# SenseTemp_-_CREAES.net
KiCad netlist of a schematic drawn in EAGLE
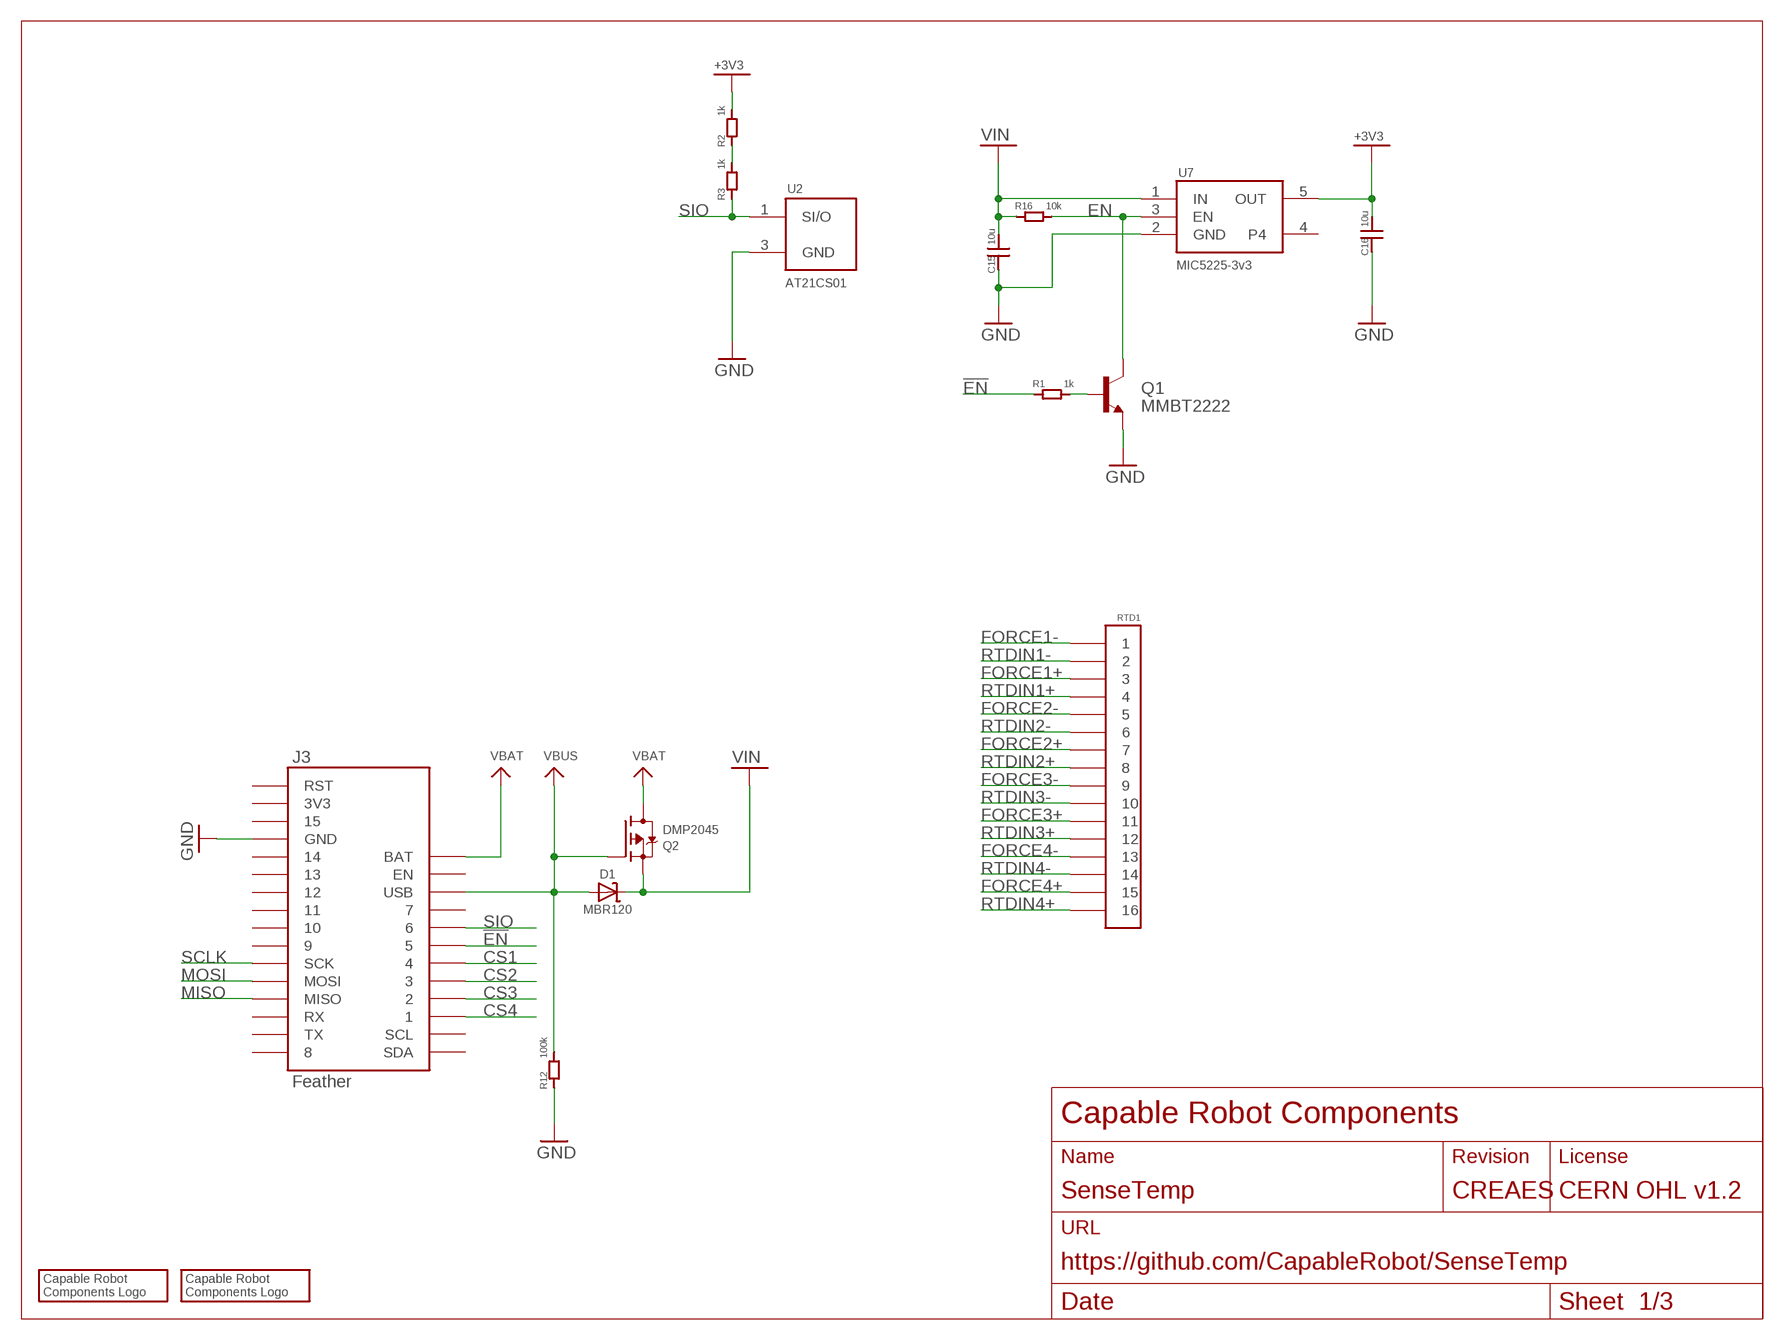
[diagram p0: schematic, sheet 1]
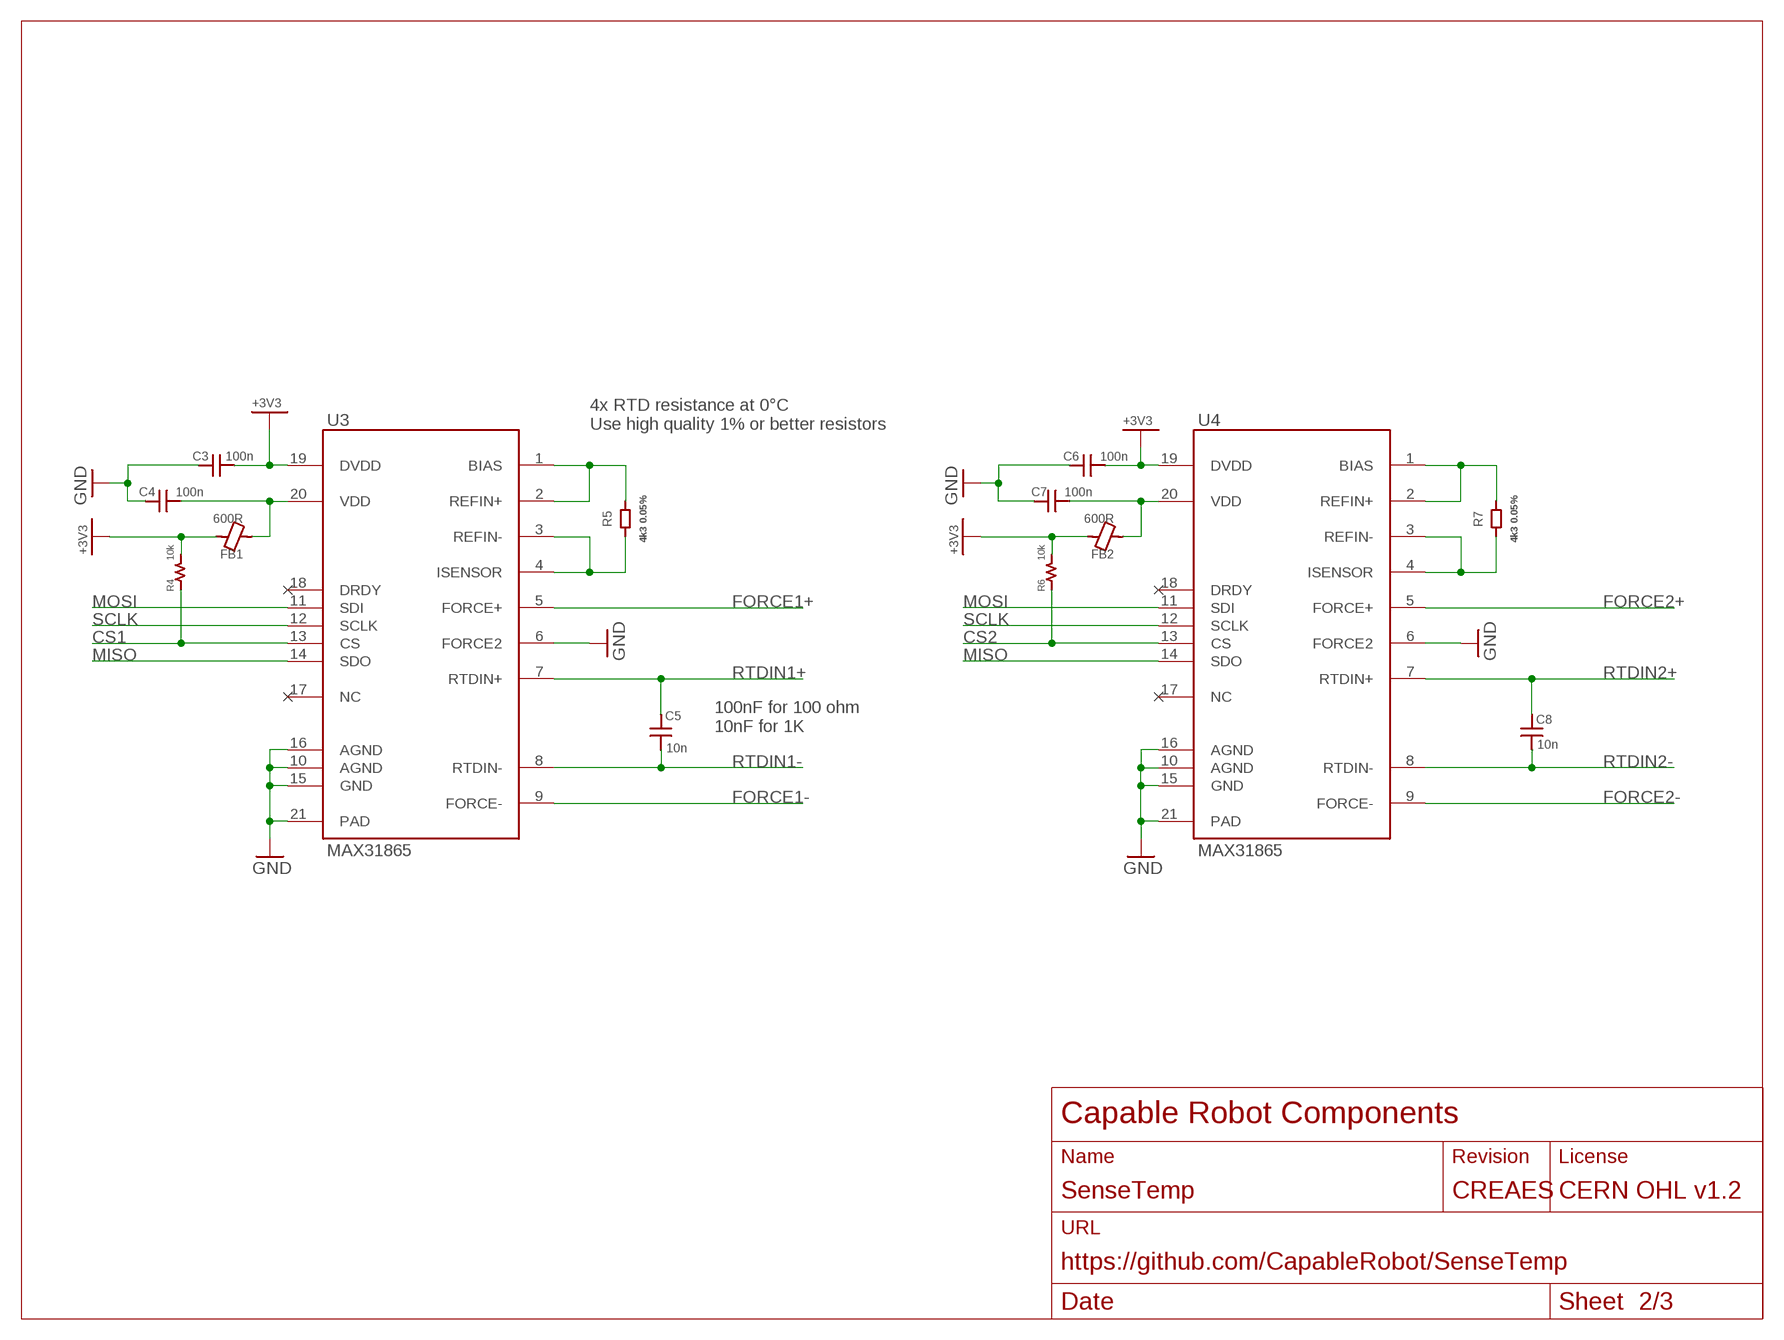
[diagram p1: schematic, sheet 2]
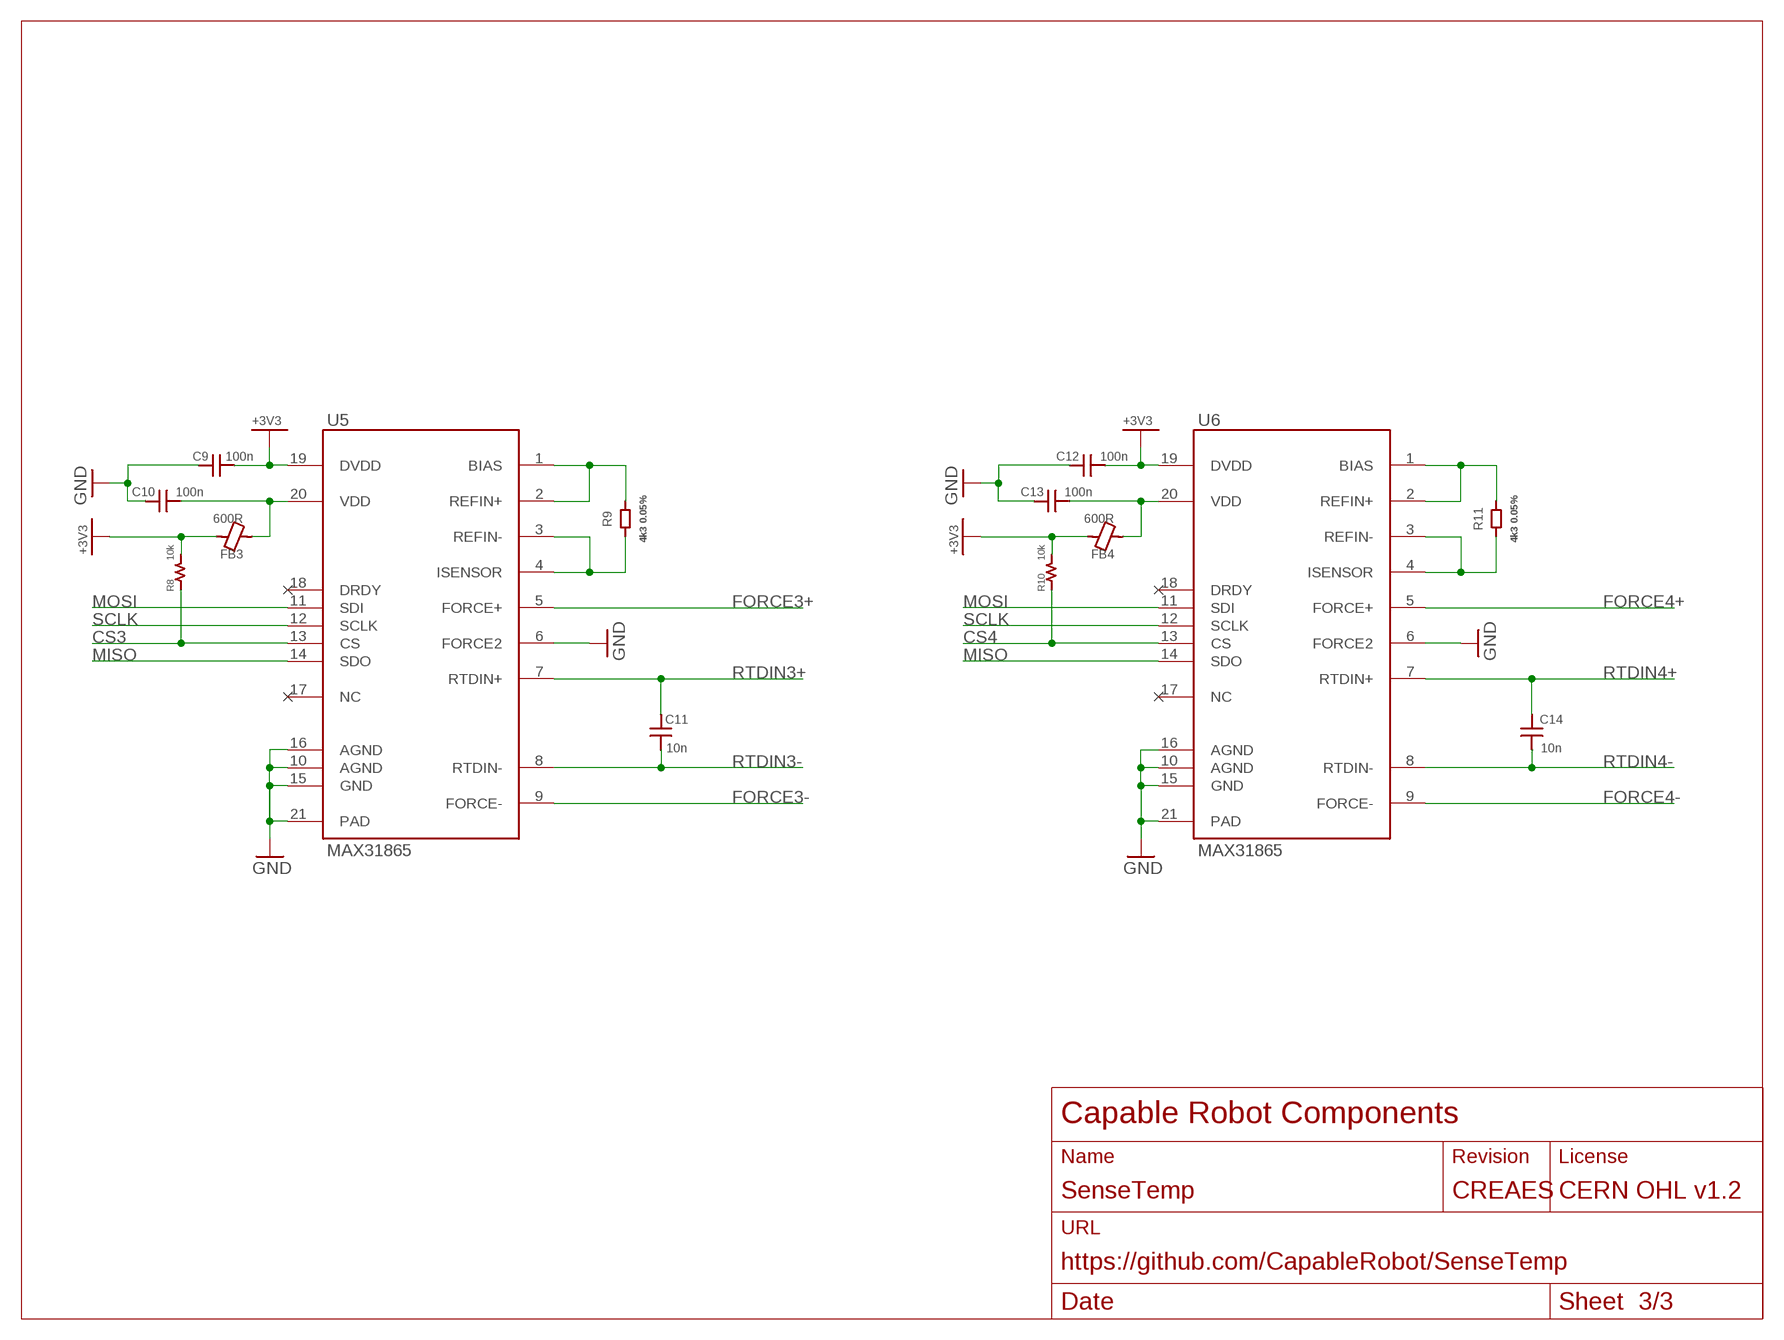
[diagram p2: schematic, sheet 3]

(export (version "E")
  (design (tool "Eeschema 10.0.6"))
  (components
    (comp (ref "C3")
      (value "100n")
      (footprint "eagle-import:0603")
      (libsource (lib "eagle-import") (part "CAP0603"))
    )
    (comp (ref "C4")
      (value "100n")
      (footprint "eagle-import:0603")
      (libsource (lib "eagle-import") (part "CAP0603"))
    )
    (comp (ref "C5")
      (value "10n")
      (footprint "eagle-import:0603")
      (libsource (lib "eagle-import") (part "CAP0603"))
    )
    (comp (ref "C6")
      (value "100n")
      (footprint "eagle-import:0603")
      (libsource (lib "eagle-import") (part "CAP0603"))
    )
    (comp (ref "C7")
      (value "100n")
      (footprint "eagle-import:0603")
      (libsource (lib "eagle-import") (part "CAP0603"))
    )
    (comp (ref "C8")
      (value "10n")
      (footprint "eagle-import:0603")
      (libsource (lib "eagle-import") (part "CAP0603"))
    )
    (comp (ref "FB1")
      (value "600R")
      (footprint "eagle-import:0603")
      (libsource (lib "eagle-import") (part "FER0603"))
    )
    (comp (ref "FB2")
      (value "600R")
      (footprint "eagle-import:0603")
      (libsource (lib "eagle-import") (part "FER0603"))
    )
    (comp (ref "R4")
      (value "10k")
      (footprint "eagle-import:0603")
      (libsource (lib "eagle-import") (part "RES0603"))
    )
    (comp (ref "R5")
      (value "4k3 0.05%")
      (footprint "eagle-import:0603")
      (libsource (lib "eagle-import") (part "CapableRobot_2153859_RES0603"))
    )
    (comp (ref "R6")
      (value "10k")
      (footprint "eagle-import:0603")
      (libsource (lib "eagle-import") (part "RES0603"))
    )
    (comp (ref "R7")
      (value "4k3 0.05%")
      (footprint "eagle-import:0603")
      (libsource (lib "eagle-import") (part "CapableRobot_2153859_RES0603"))
    )
    (comp (ref "U3")
      (value "MAX31865")
      (footprint "eagle-import:QFN65P500X500X100-21T325")
      (libsource (lib "eagle-import") (part "MAX31865"))
    )
    (comp (ref "U4")
      (value "MAX31865")
      (footprint "eagle-import:QFN65P500X500X100-21T325")
      (libsource (lib "eagle-import") (part "MAX31865"))
    )
    (comp (ref "C9")
      (value "100n")
      (footprint "eagle-import:0603")
      (libsource (lib "eagle-import") (part "CAP0603"))
    )
    (comp (ref "C10")
      (value "100n")
      (footprint "eagle-import:0603")
      (libsource (lib "eagle-import") (part "CAP0603"))
    )
    (comp (ref "C11")
      (value "10n")
      (footprint "eagle-import:0603")
      (libsource (lib "eagle-import") (part "CAP0603"))
    )
    (comp (ref "C12")
      (value "100n")
      (footprint "eagle-import:0603")
      (libsource (lib "eagle-import") (part "CAP0603"))
    )
    (comp (ref "C13")
      (value "100n")
      (footprint "eagle-import:0603")
      (libsource (lib "eagle-import") (part "CAP0603"))
    )
    (comp (ref "C14")
      (value "10n")
      (footprint "eagle-import:0603")
      (libsource (lib "eagle-import") (part "CAP0603"))
    )
    (comp (ref "FB3")
      (value "600R")
      (footprint "eagle-import:0603")
      (libsource (lib "eagle-import") (part "FER0603"))
    )
    (comp (ref "FB4")
      (value "600R")
      (footprint "eagle-import:0603")
      (libsource (lib "eagle-import") (part "FER0603"))
    )
    (comp (ref "R8")
      (value "10k")
      (footprint "eagle-import:0603")
      (libsource (lib "eagle-import") (part "RES0603"))
    )
    (comp (ref "R9")
      (value "4k3 0.05%")
      (footprint "eagle-import:0603")
      (libsource (lib "eagle-import") (part "CapableRobot_2153859_RES0603"))
    )
    (comp (ref "R10")
      (value "10k")
      (footprint "eagle-import:0603")
      (libsource (lib "eagle-import") (part "RES0603"))
    )
    (comp (ref "R11")
      (value "4k3 0.05%")
      (footprint "eagle-import:0603")
      (libsource (lib "eagle-import") (part "CapableRobot_2153859_RES0603"))
    )
    (comp (ref "U5")
      (value "MAX31865")
      (footprint "eagle-import:QFN65P500X500X100-21T325")
      (libsource (lib "eagle-import") (part "MAX31865"))
    )
    (comp (ref "U6")
      (value "MAX31865")
      (footprint "eagle-import:QFN65P500X500X100-21T325")
      (libsource (lib "eagle-import") (part "MAX31865"))
    )
    (comp (ref "C15")
      (value "10u")
      (footprint "eagle-import:0805")
      (libsource (lib "eagle-import") (part "CAP0805"))
    )
    (comp (ref "C16")
      (value "10u")
      (footprint "eagle-import:0805")
      (libsource (lib "eagle-import") (part "CAP0805"))
    )
    (comp (ref "D1")
      (value "MBR120")
      (footprint "eagle-import:SOD-123")
      (fields (field (name "MPN") "MBR120VLSFT3G"))
      (libsource (lib "eagle-import") (part "DIODE-SCHOTTKYSOD-123"))
    )
    (comp (ref "J3")
      (value "FEATHERPTH")
      (footprint "eagle-import:FEATHER-PTH")
      (libsource (lib "eagle-import") (part "FEATHERPTH"))
    )
    (comp (ref "LOGO1")
      (value "CRC-LOGO7SILK")
      (footprint "eagle-import:CRC-LOGO-7-SILK")
      (libsource (lib "eagle-import") (part "CRC-LOGO7SILK"))
    )
    (comp (ref "LOGO2")
      (value "CRC-LOGO5")
      (footprint "eagle-import:CRC-LOGO-5")
      (libsource (lib "eagle-import") (part "CRC-LOGO5"))
    )
    (comp (ref "Q1")
      (value "MMBT2222")
      (footprint "eagle-import:SOT23-3")
      (fields (field (name "MPN") "MMBT2222LT1G"))
      (libsource (lib "eagle-import") (part "TRANSISTOR_NPNSOT23-3"))
    )
    (comp (ref "Q2")
      (value "DMP2045")
      (footprint "eagle-import:SOT23-R")
      (fields (field (name "MPN") "DMP2045U-7"))
      (libsource (lib "eagle-import") (part "MOSFET-P"))
    )
    (comp (ref "R1")
      (value "1k")
      (footprint "eagle-import:0603")
      (libsource (lib "eagle-import") (part "CapableRobot_2153859_RES0603"))
    )
    (comp (ref "R2")
      (value "1k")
      (footprint "eagle-import:0603")
      (libsource (lib "eagle-import") (part "CapableRobot_2153859_RES0603"))
    )
    (comp (ref "R3")
      (value "1k")
      (footprint "eagle-import:0603")
      (libsource (lib "eagle-import") (part "CapableRobot_2153859_RES0603"))
    )
    (comp (ref "R12")
      (value "100k")
      (footprint "eagle-import:0603")
      (libsource (lib "eagle-import") (part "CapableRobot_2153859_RES0603"))
    )
    (comp (ref "R16")
      (value "10k")
      (footprint "eagle-import:0603")
      (libsource (lib "eagle-import") (part "CapableRobot_2153859_RES0603"))
    )
    (comp (ref "RTD1")
      (value "CONN-16ZT")
      (footprint "eagle-import:CONN-2X8-050-SMT-ZT")
      (fields (field (name "MPN") "3221-16-0300-00"))
      (libsource (lib "eagle-import") (part "CONN-16ZT"))
    )
    (comp (ref "U2")
      (value "AT21CS01")
      (footprint "eagle-import:SOT23")
      (libsource (lib "eagle-import") (part "AT21CS01"))
    )
    (comp (ref "U7")
      (value "3v3")
      (footprint "eagle-import:SOT25")
      (libsource (lib "eagle-import") (part "MIC5225"))
    )
  )
  (nets
    (net (code "1") (name "+3V3") (class "Default")
      (node (ref "C12") (pin "1") (pinfunction "P$1_1") (pintype "bidirectional"))
      (node (ref "C16") (pin "2") (pinfunction "P$2_2") (pintype "bidirectional"))
      (node (ref "C3") (pin "1") (pinfunction "P$1_1") (pintype "bidirectional"))
      (node (ref "C6") (pin "1") (pinfunction "P$1_1") (pintype "bidirectional"))
      (node (ref "C9") (pin "1") (pinfunction "P$1_1") (pintype "bidirectional"))
      (node (ref "FB1") (pin "2") (pinfunction "P$2_2") (pintype "bidirectional"))
      (node (ref "FB2") (pin "2") (pinfunction "P$2_2") (pintype "bidirectional"))
      (node (ref "FB3") (pin "2") (pinfunction "P$2_2") (pintype "bidirectional"))
      (node (ref "FB4") (pin "2") (pinfunction "P$2_2") (pintype "bidirectional"))
      (node (ref "R10") (pin "2") (pinfunction "2_2") (pintype "passive"))
      (node (ref "R2") (pin "2") (pinfunction "2_2") (pintype "passive"))
      (node (ref "R4") (pin "2") (pinfunction "2_2") (pintype "passive"))
      (node (ref "R6") (pin "2") (pinfunction "2_2") (pintype "passive"))
      (node (ref "R8") (pin "2") (pinfunction "2_2") (pintype "passive"))
      (node (ref "U3") (pin "19") (pinfunction "DVDD_19") (pintype "bidirectional"))
      (node (ref "U4") (pin "19") (pinfunction "DVDD_19") (pintype "bidirectional"))
      (node (ref "U5") (pin "19") (pinfunction "DVDD_19") (pintype "bidirectional"))
      (node (ref "U6") (pin "19") (pinfunction "DVDD_19") (pintype "bidirectional"))
      (node (ref "U7") (pin "5") (pinfunction "OUT_5") (pintype "bidirectional"))
    )
    (net (code "2") (name "CS1") (class "Default")
      (node (ref "J3") (pin "4") (pinfunction "4_4") (pintype "bidirectional"))
      (node (ref "R4") (pin "1") (pinfunction "1_1") (pintype "passive"))
      (node (ref "U3") (pin "13") (pinfunction "CS_13") (pintype "bidirectional"))
    )
    (net (code "3") (name "CS2") (class "Default")
      (node (ref "J3") (pin "3") (pinfunction "3_3") (pintype "bidirectional"))
      (node (ref "R6") (pin "1") (pinfunction "1_1") (pintype "passive"))
      (node (ref "U4") (pin "13") (pinfunction "CS_13") (pintype "bidirectional"))
    )
    (net (code "4") (name "CS3") (class "Default")
      (node (ref "J3") (pin "2") (pinfunction "2_2") (pintype "bidirectional"))
      (node (ref "R8") (pin "1") (pinfunction "1_1") (pintype "passive"))
      (node (ref "U5") (pin "13") (pinfunction "CS_13") (pintype "bidirectional"))
    )
    (net (code "5") (name "CS4") (class "Default")
      (node (ref "J3") (pin "1") (pinfunction "1_1") (pintype "bidirectional"))
      (node (ref "R10") (pin "1") (pinfunction "1_1") (pintype "passive"))
      (node (ref "U6") (pin "13") (pinfunction "CS_13") (pintype "bidirectional"))
    )
    (net (code "6") (name "EN") (class "Default")
      (node (ref "Q1") (pin "3") (pinfunction "C_3") (pintype "passive"))
      (node (ref "R16") (pin "2") (pinfunction "2_2") (pintype "passive"))
      (node (ref "U7") (pin "3") (pinfunction "EN_3") (pintype "bidirectional"))
    )
    (net (code "7") (name "FORCE1+") (class "Default")
      (node (ref "RTD1") (pin "3") (pinfunction "3_3") (pintype "bidirectional"))
      (node (ref "U3") (pin "5") (pinfunction "FORCE+_5") (pintype "bidirectional"))
    )
    (net (code "8") (name "FORCE1-") (class "Default")
      (node (ref "RTD1") (pin "1") (pinfunction "1_1") (pintype "bidirectional"))
      (node (ref "U3") (pin "9") (pinfunction "FORCE-_9") (pintype "bidirectional"))
    )
    (net (code "9") (name "FORCE2+") (class "Default")
      (node (ref "RTD1") (pin "7") (pinfunction "7_7") (pintype "bidirectional"))
      (node (ref "U4") (pin "5") (pinfunction "FORCE+_5") (pintype "bidirectional"))
    )
    (net (code "10") (name "FORCE2-") (class "Default")
      (node (ref "RTD1") (pin "5") (pinfunction "5_5") (pintype "bidirectional"))
      (node (ref "U4") (pin "9") (pinfunction "FORCE-_9") (pintype "bidirectional"))
    )
    (net (code "11") (name "FORCE3+") (class "Default")
      (node (ref "RTD1") (pin "11") (pinfunction "11_11") (pintype "bidirectional"))
      (node (ref "U5") (pin "5") (pinfunction "FORCE+_5") (pintype "bidirectional"))
    )
    (net (code "12") (name "FORCE3-") (class "Default")
      (node (ref "RTD1") (pin "9") (pinfunction "9_9") (pintype "bidirectional"))
      (node (ref "U5") (pin "9") (pinfunction "FORCE-_9") (pintype "bidirectional"))
    )
    (net (code "13") (name "FORCE4+") (class "Default")
      (node (ref "RTD1") (pin "15") (pinfunction "15_15") (pintype "bidirectional"))
      (node (ref "U6") (pin "5") (pinfunction "FORCE+_5") (pintype "bidirectional"))
    )
    (net (code "14") (name "FORCE4-") (class "Default")
      (node (ref "RTD1") (pin "13") (pinfunction "13_13") (pintype "bidirectional"))
      (node (ref "U6") (pin "9") (pinfunction "FORCE-_9") (pintype "bidirectional"))
    )
    (net (code "15") (name "GND") (class "Default")
      (node (ref "C10") (pin "2") (pinfunction "P$2_2") (pintype "bidirectional"))
      (node (ref "C12") (pin "2") (pinfunction "P$2_2") (pintype "bidirectional"))
      (node (ref "C13") (pin "2") (pinfunction "P$2_2") (pintype "bidirectional"))
      (node (ref "C15") (pin "1") (pinfunction "P$1_1") (pintype "bidirectional"))
      (node (ref "C16") (pin "1") (pinfunction "P$1_1") (pintype "bidirectional"))
      (node (ref "C3") (pin "2") (pinfunction "P$2_2") (pintype "bidirectional"))
      (node (ref "C4") (pin "2") (pinfunction "P$2_2") (pintype "bidirectional"))
      (node (ref "C6") (pin "2") (pinfunction "P$2_2") (pintype "bidirectional"))
      (node (ref "C7") (pin "2") (pinfunction "P$2_2") (pintype "bidirectional"))
      (node (ref "C9") (pin "2") (pinfunction "P$2_2") (pintype "bidirectional"))
      (node (ref "J3") (pin "GND") (pinfunction "GND_GND") (pintype "bidirectional"))
      (node (ref "Q1") (pin "2") (pinfunction "E_2") (pintype "passive"))
      (node (ref "R12") (pin "1") (pinfunction "1_1") (pintype "passive"))
      (node (ref "U2") (pin "3") (pinfunction "GND_3") (pintype "bidirectional"))
      (node (ref "U3") (pin "10") (pinfunction "AGND_10") (pintype "bidirectional"))
      (node (ref "U3") (pin "15") (pinfunction "GND_15") (pintype "bidirectional"))
      (node (ref "U3") (pin "16") (pinfunction "AGND_16") (pintype "bidirectional"))
      (node (ref "U3") (pin "21") (pinfunction "PAD_21") (pintype "bidirectional"))
      (node (ref "U3") (pin "6") (pinfunction "FORCE2_6") (pintype "bidirectional"))
      (node (ref "U4") (pin "10") (pinfunction "AGND_10") (pintype "bidirectional"))
      (node (ref "U4") (pin "15") (pinfunction "GND_15") (pintype "bidirectional"))
      (node (ref "U4") (pin "16") (pinfunction "AGND_16") (pintype "bidirectional"))
      (node (ref "U4") (pin "21") (pinfunction "PAD_21") (pintype "bidirectional"))
      (node (ref "U4") (pin "6") (pinfunction "FORCE2_6") (pintype "bidirectional"))
      (node (ref "U5") (pin "10") (pinfunction "AGND_10") (pintype "bidirectional"))
      (node (ref "U5") (pin "15") (pinfunction "GND_15") (pintype "bidirectional"))
      (node (ref "U5") (pin "16") (pinfunction "AGND_16") (pintype "bidirectional"))
      (node (ref "U5") (pin "21") (pinfunction "PAD_21") (pintype "bidirectional"))
      (node (ref "U5") (pin "6") (pinfunction "FORCE2_6") (pintype "bidirectional"))
      (node (ref "U6") (pin "10") (pinfunction "AGND_10") (pintype "bidirectional"))
      (node (ref "U6") (pin "15") (pinfunction "GND_15") (pintype "bidirectional"))
      (node (ref "U6") (pin "16") (pinfunction "AGND_16") (pintype "bidirectional"))
      (node (ref "U6") (pin "21") (pinfunction "PAD_21") (pintype "bidirectional"))
      (node (ref "U6") (pin "6") (pinfunction "FORCE2_6") (pintype "bidirectional"))
      (node (ref "U7") (pin "2") (pinfunction "GND_2") (pintype "bidirectional"))
    )
    (net (code "16") (name "MISO") (class "Default")
      (node (ref "J3") (pin "MISO") (pinfunction "MISO_MISO") (pintype "bidirectional"))
      (node (ref "U3") (pin "14") (pinfunction "SDO_14") (pintype "bidirectional"))
      (node (ref "U4") (pin "14") (pinfunction "SDO_14") (pintype "bidirectional"))
      (node (ref "U5") (pin "14") (pinfunction "SDO_14") (pintype "bidirectional"))
      (node (ref "U6") (pin "14") (pinfunction "SDO_14") (pintype "bidirectional"))
    )
    (net (code "17") (name "MOSI") (class "Default")
      (node (ref "J3") (pin "MOSI") (pinfunction "MOSI_MOSI") (pintype "bidirectional"))
      (node (ref "U3") (pin "11") (pinfunction "SDI_11") (pintype "bidirectional"))
      (node (ref "U4") (pin "11") (pinfunction "SDI_11") (pintype "bidirectional"))
      (node (ref "U5") (pin "11") (pinfunction "SDI_11") (pintype "bidirectional"))
      (node (ref "U6") (pin "11") (pinfunction "SDI_11") (pintype "bidirectional"))
    )
    (net (code "18") (name "Net-(C4-P$1)") (class "Default")
      (node (ref "C4") (pin "1") (pinfunction "P$1_1") (pintype "bidirectional"))
      (node (ref "FB1") (pin "1") (pinfunction "P$1_1") (pintype "bidirectional"))
      (node (ref "U3") (pin "20") (pinfunction "VDD_20") (pintype "bidirectional"))
    )
    (net (code "19") (name "Net-(C7-P$1)") (class "Default")
      (node (ref "C7") (pin "1") (pinfunction "P$1_1") (pintype "bidirectional"))
      (node (ref "FB2") (pin "1") (pinfunction "P$1_1") (pintype "bidirectional"))
      (node (ref "U4") (pin "20") (pinfunction "VDD_20") (pintype "bidirectional"))
    )
    (net (code "20") (name "Net-(C10-P$1)") (class "Default")
      (node (ref "C10") (pin "1") (pinfunction "P$1_1") (pintype "bidirectional"))
      (node (ref "FB3") (pin "1") (pinfunction "P$1_1") (pintype "bidirectional"))
      (node (ref "U5") (pin "20") (pinfunction "VDD_20") (pintype "bidirectional"))
    )
    (net (code "21") (name "Net-(C13-P$1)") (class "Default")
      (node (ref "C13") (pin "1") (pinfunction "P$1_1") (pintype "bidirectional"))
      (node (ref "FB4") (pin "1") (pinfunction "P$1_1") (pintype "bidirectional"))
      (node (ref "U6") (pin "20") (pinfunction "VDD_20") (pintype "bidirectional"))
    )
    (net (code "22") (name "Net-(Q1-B)") (class "Default")
      (node (ref "Q1") (pin "1") (pinfunction "B_1") (pintype "passive"))
      (node (ref "R1") (pin "2") (pinfunction "2_2") (pintype "passive"))
    )
    (net (code "23") (name "Net-(R2-Pad1)") (class "Default")
      (node (ref "R2") (pin "1") (pinfunction "1_1") (pintype "passive"))
      (node (ref "R3") (pin "2") (pinfunction "2_2") (pintype "passive"))
    )
    (net (code "24") (name "Net-(U3-BIAS)") (class "Default")
      (node (ref "R5") (pin "2") (pinfunction "2_2") (pintype "passive"))
      (node (ref "U3") (pin "1") (pinfunction "BIAS_1") (pintype "bidirectional"))
      (node (ref "U3") (pin "2") (pinfunction "REFIN+_2") (pintype "bidirectional"))
    )
    (net (code "25") (name "Net-(U3-ISENSOR)") (class "Default")
      (node (ref "R5") (pin "1") (pinfunction "1_1") (pintype "passive"))
      (node (ref "U3") (pin "3") (pinfunction "REFIN-_3") (pintype "bidirectional"))
      (node (ref "U3") (pin "4") (pinfunction "ISENSOR_4") (pintype "bidirectional"))
    )
    (net (code "26") (name "Net-(U4-BIAS)") (class "Default")
      (node (ref "R7") (pin "2") (pinfunction "2_2") (pintype "passive"))
      (node (ref "U4") (pin "1") (pinfunction "BIAS_1") (pintype "bidirectional"))
      (node (ref "U4") (pin "2") (pinfunction "REFIN+_2") (pintype "bidirectional"))
    )
    (net (code "27") (name "Net-(U4-ISENSOR)") (class "Default")
      (node (ref "R7") (pin "1") (pinfunction "1_1") (pintype "passive"))
      (node (ref "U4") (pin "3") (pinfunction "REFIN-_3") (pintype "bidirectional"))
      (node (ref "U4") (pin "4") (pinfunction "ISENSOR_4") (pintype "bidirectional"))
    )
    (net (code "28") (name "Net-(U5-BIAS)") (class "Default")
      (node (ref "R9") (pin "2") (pinfunction "2_2") (pintype "passive"))
      (node (ref "U5") (pin "1") (pinfunction "BIAS_1") (pintype "bidirectional"))
      (node (ref "U5") (pin "2") (pinfunction "REFIN+_2") (pintype "bidirectional"))
    )
    (net (code "29") (name "Net-(U5-ISENSOR)") (class "Default")
      (node (ref "R9") (pin "1") (pinfunction "1_1") (pintype "passive"))
      (node (ref "U5") (pin "3") (pinfunction "REFIN-_3") (pintype "bidirectional"))
      (node (ref "U5") (pin "4") (pinfunction "ISENSOR_4") (pintype "bidirectional"))
    )
    (net (code "30") (name "Net-(U6-BIAS)") (class "Default")
      (node (ref "R11") (pin "2") (pinfunction "2_2") (pintype "passive"))
      (node (ref "U6") (pin "1") (pinfunction "BIAS_1") (pintype "bidirectional"))
      (node (ref "U6") (pin "2") (pinfunction "REFIN+_2") (pintype "bidirectional"))
    )
    (net (code "31") (name "Net-(U6-ISENSOR)") (class "Default")
      (node (ref "R11") (pin "1") (pinfunction "1_1") (pintype "passive"))
      (node (ref "U6") (pin "3") (pinfunction "REFIN-_3") (pintype "bidirectional"))
      (node (ref "U6") (pin "4") (pinfunction "ISENSOR_4") (pintype "bidirectional"))
    )
    (net (code "32") (name "RTDIN1+") (class "Default")
      (node (ref "C5") (pin "1") (pinfunction "P$1_1") (pintype "bidirectional"))
      (node (ref "RTD1") (pin "4") (pinfunction "4_4") (pintype "bidirectional"))
      (node (ref "U3") (pin "7") (pinfunction "RTDIN+_7") (pintype "bidirectional"))
    )
    (net (code "33") (name "RTDIN1-") (class "Default")
      (node (ref "C5") (pin "2") (pinfunction "P$2_2") (pintype "bidirectional"))
      (node (ref "RTD1") (pin "2") (pinfunction "2_2") (pintype "bidirectional"))
      (node (ref "U3") (pin "8") (pinfunction "RTDIN-_8") (pintype "bidirectional"))
    )
    (net (code "34") (name "RTDIN2+") (class "Default")
      (node (ref "C8") (pin "1") (pinfunction "P$1_1") (pintype "bidirectional"))
      (node (ref "RTD1") (pin "8") (pinfunction "8_8") (pintype "bidirectional"))
      (node (ref "U4") (pin "7") (pinfunction "RTDIN+_7") (pintype "bidirectional"))
    )
    (net (code "35") (name "RTDIN2-") (class "Default")
      (node (ref "C8") (pin "2") (pinfunction "P$2_2") (pintype "bidirectional"))
      (node (ref "RTD1") (pin "6") (pinfunction "6_6") (pintype "bidirectional"))
      (node (ref "U4") (pin "8") (pinfunction "RTDIN-_8") (pintype "bidirectional"))
    )
    (net (code "36") (name "RTDIN3+") (class "Default")
      (node (ref "C11") (pin "1") (pinfunction "P$1_1") (pintype "bidirectional"))
      (node (ref "RTD1") (pin "12") (pinfunction "12_12") (pintype "bidirectional"))
      (node (ref "U5") (pin "7") (pinfunction "RTDIN+_7") (pintype "bidirectional"))
    )
    (net (code "37") (name "RTDIN3-") (class "Default")
      (node (ref "C11") (pin "2") (pinfunction "P$2_2") (pintype "bidirectional"))
      (node (ref "RTD1") (pin "10") (pinfunction "10_10") (pintype "bidirectional"))
      (node (ref "U5") (pin "8") (pinfunction "RTDIN-_8") (pintype "bidirectional"))
    )
    (net (code "38") (name "RTDIN4+") (class "Default")
      (node (ref "C14") (pin "1") (pinfunction "P$1_1") (pintype "bidirectional"))
      (node (ref "RTD1") (pin "16") (pinfunction "16_16") (pintype "bidirectional"))
      (node (ref "U6") (pin "7") (pinfunction "RTDIN+_7") (pintype "bidirectional"))
    )
    (net (code "39") (name "RTDIN4-") (class "Default")
      (node (ref "C14") (pin "2") (pinfunction "P$2_2") (pintype "bidirectional"))
      (node (ref "RTD1") (pin "14") (pinfunction "14_14") (pintype "bidirectional"))
      (node (ref "U6") (pin "8") (pinfunction "RTDIN-_8") (pintype "bidirectional"))
    )
    (net (code "40") (name "SCLK") (class "Default")
      (node (ref "J3") (pin "SCK") (pinfunction "SCK_SCK") (pintype "bidirectional"))
      (node (ref "U3") (pin "12") (pinfunction "SCLK_12") (pintype "bidirectional"))
      (node (ref "U4") (pin "12") (pinfunction "SCLK_12") (pintype "bidirectional"))
      (node (ref "U5") (pin "12") (pinfunction "SCLK_12") (pintype "bidirectional"))
      (node (ref "U6") (pin "12") (pinfunction "SCLK_12") (pintype "bidirectional"))
    )
    (net (code "41") (name "SIO") (class "Default")
      (node (ref "J3") (pin "6") (pinfunction "6_6") (pintype "bidirectional"))
      (node (ref "R3") (pin "1") (pinfunction "1_1") (pintype "passive"))
      (node (ref "U2") (pin "1") (pinfunction "SI/O_1") (pintype "bidirectional"))
    )
    (net (code "42") (name "VBAT") (class "Default")
      (node (ref "J3") (pin "BAT") (pinfunction "BAT_BAT") (pintype "bidirectional"))
      (node (ref "Q2") (pin "3") (pinfunction "D_3") (pintype "passive"))
    )
    (net (code "43") (name "VBUS") (class "Default")
      (node (ref "D1") (pin "A") (pinfunction "A_A") (pintype "passive"))
      (node (ref "J3") (pin "USB") (pinfunction "USB_USB") (pintype "bidirectional"))
      (node (ref "Q2") (pin "1") (pinfunction "G_1") (pintype "passive"))
      (node (ref "R12") (pin "2") (pinfunction "2_2") (pintype "passive"))
    )
    (net (code "44") (name "VIN") (class "Default")
      (node (ref "C15") (pin "2") (pinfunction "P$2_2") (pintype "bidirectional"))
      (node (ref "D1") (pin "C") (pinfunction "C_C") (pintype "passive"))
      (node (ref "Q2") (pin "2") (pinfunction "S_2") (pintype "passive"))
      (node (ref "R16") (pin "1") (pinfunction "1_1") (pintype "passive"))
      (node (ref "U7") (pin "1") (pinfunction "IN_1") (pintype "bidirectional"))
    )
    (net (code "45") (name "unconnected-(J3-Pad3V3)") (class "Default")
      (node (ref "J3") (pin "3V3") (pinfunction "3V3_3V3") (pintype "bidirectional"))
    )
    (net (code "46") (name "unconnected-(J3-Pad7)") (class "Default")
      (node (ref "J3") (pin "7") (pinfunction "7_7") (pintype "bidirectional"))
    )
    (net (code "47") (name "unconnected-(J3-Pad8)") (class "Default")
      (node (ref "J3") (pin "8") (pinfunction "8_8") (pintype "bidirectional"))
    )
    (net (code "48") (name "unconnected-(J3-Pad9)") (class "Default")
      (node (ref "J3") (pin "9") (pinfunction "9_9") (pintype "bidirectional"))
    )
    (net (code "49") (name "unconnected-(J3-Pad10)") (class "Default")
      (node (ref "J3") (pin "10") (pinfunction "10_10") (pintype "bidirectional"))
    )
    (net (code "50") (name "unconnected-(J3-Pad11)") (class "Default")
      (node (ref "J3") (pin "11") (pinfunction "11_11") (pintype "bidirectional"))
    )
    (net (code "51") (name "unconnected-(J3-Pad12)") (class "Default")
      (node (ref "J3") (pin "12") (pinfunction "12_12") (pintype "bidirectional"))
    )
    (net (code "52") (name "unconnected-(J3-Pad13)") (class "Default")
      (node (ref "J3") (pin "13") (pinfunction "13_13") (pintype "bidirectional"))
    )
    (net (code "53") (name "unconnected-(J3-Pad14)") (class "Default")
      (node (ref "J3") (pin "14") (pinfunction "14_14") (pintype "bidirectional"))
    )
    (net (code "54") (name "unconnected-(J3-Pad15)") (class "Default")
      (node (ref "J3") (pin "15") (pinfunction "15_15") (pintype "bidirectional"))
    )
    (net (code "55") (name "unconnected-(J3-PadEN)") (class "Default")
      (node (ref "J3") (pin "EN") (pinfunction "EN_EN") (pintype "bidirectional"))
    )
    (net (code "56") (name "unconnected-(J3-PadRST)") (class "Default")
      (node (ref "J3") (pin "RST") (pinfunction "RST_RST") (pintype "bidirectional"))
    )
    (net (code "57") (name "unconnected-(J3-PadRX)") (class "Default")
      (node (ref "J3") (pin "RX") (pinfunction "RX_RX") (pintype "bidirectional"))
    )
    (net (code "58") (name "unconnected-(J3-PadSCL)") (class "Default")
      (node (ref "J3") (pin "SCL") (pinfunction "SCL_SCL") (pintype "bidirectional"))
    )
    (net (code "59") (name "unconnected-(J3-PadSDA)") (class "Default")
      (node (ref "J3") (pin "SDA") (pinfunction "SDA_SDA") (pintype "bidirectional"))
    )
    (net (code "60") (name "unconnected-(J3-PadTX)") (class "Default")
      (node (ref "J3") (pin "TX") (pinfunction "TX_TX") (pintype "bidirectional"))
    )
    (net (code "61") (name "unconnected-(U3-DRDY-Pad18)") (class "Default")
      (node (ref "U3") (pin "18") (pinfunction "DRDY_18") (pintype "bidirectional"))
    )
    (net (code "62") (name "unconnected-(U3-NC-Pad17)") (class "Default")
      (node (ref "U3") (pin "17") (pinfunction "NC_17") (pintype "bidirectional"))
    )
    (net (code "63") (name "unconnected-(U4-DRDY-Pad18)") (class "Default")
      (node (ref "U4") (pin "18") (pinfunction "DRDY_18") (pintype "bidirectional"))
    )
    (net (code "64") (name "unconnected-(U4-NC-Pad17)") (class "Default")
      (node (ref "U4") (pin "17") (pinfunction "NC_17") (pintype "bidirectional"))
    )
    (net (code "65") (name "unconnected-(U5-DRDY-Pad18)") (class "Default")
      (node (ref "U5") (pin "18") (pinfunction "DRDY_18") (pintype "bidirectional"))
    )
    (net (code "66") (name "unconnected-(U5-NC-Pad17)") (class "Default")
      (node (ref "U5") (pin "17") (pinfunction "NC_17") (pintype "bidirectional"))
    )
    (net (code "67") (name "unconnected-(U6-DRDY-Pad18)") (class "Default")
      (node (ref "U6") (pin "18") (pinfunction "DRDY_18") (pintype "bidirectional"))
    )
    (net (code "68") (name "unconnected-(U6-NC-Pad17)") (class "Default")
      (node (ref "U6") (pin "17") (pinfunction "NC_17") (pintype "bidirectional"))
    )
    (net (code "69") (name "unconnected-(U7-P4-Pad4)") (class "Default")
      (node (ref "U7") (pin "4") (pinfunction "P4_4") (pintype "bidirectional"))
    )
    (net (code "70") (name "~{EN}") (class "Default")
      (node (ref "J3") (pin "5") (pinfunction "5_5") (pintype "bidirectional"))
      (node (ref "R1") (pin "1") (pinfunction "1_1") (pintype "passive"))
    )
  )
)
